# ssslidar_v1_0_blade_PWR_top.net
KiCad netlist of a schematic drawn in EAGLE
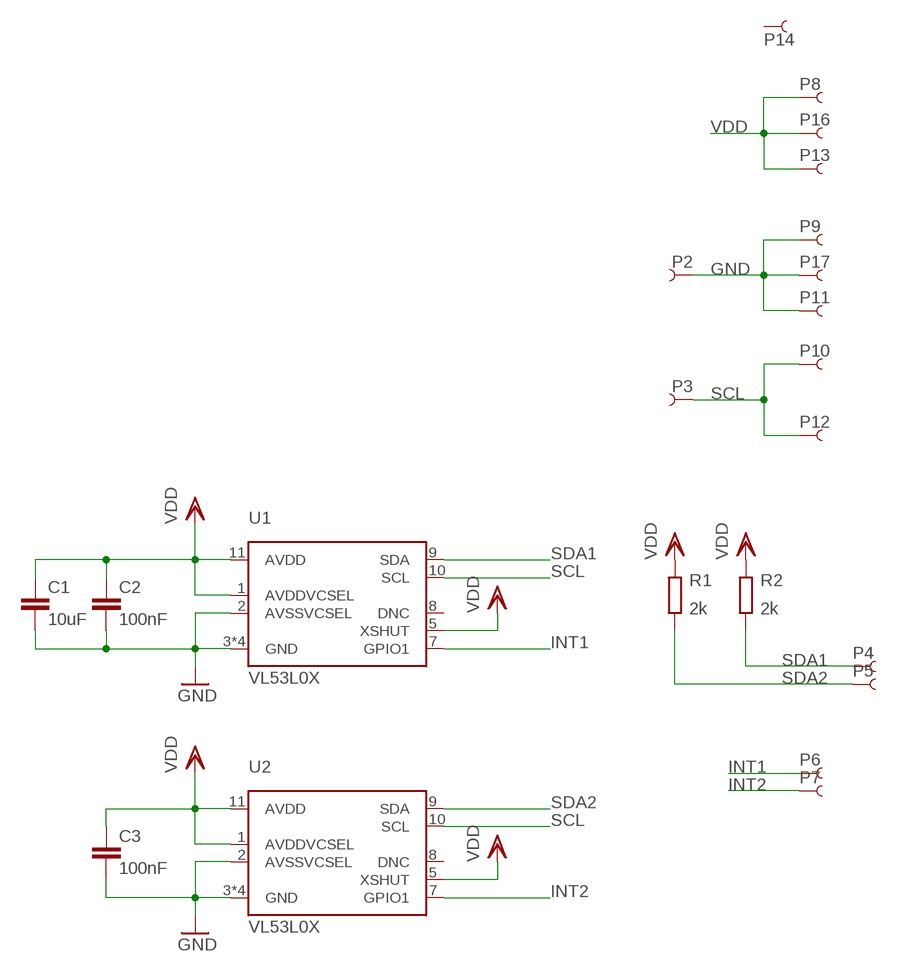
[diagram p0: schematic, sheet 1]

(export (version "E")
  (design (tool "Eeschema 10.0.6"))
  (components
    (comp (ref "C1")
      (value "10uF")
      (footprint "eagle-import:0805_N")
      (libsource (lib "eagle-import") (part "C0805"))
    )
    (comp (ref "C2")
      (value "100nF")
      (footprint "eagle-import:0402_N")
      (libsource (lib "eagle-import") (part "C0402"))
    )
    (comp (ref "C3")
      (value "100nF")
      (footprint "eagle-import:0402_N")
      (libsource (lib "eagle-import") (part "C0402"))
    )
    (comp (ref "P2")
      (value "PIN_SMD_1X1_RECT")
      (footprint "eagle-import:PIN_SMD_1X1_RECT")
      (libsource (lib "eagle-import") (part "PIN_SMD_1X1_RECT"))
    )
    (comp (ref "P3")
      (value "PIN_SMD_0.8X1_RECT")
      (footprint "eagle-import:PIN_SMD_0.8X1_RECT")
      (libsource (lib "eagle-import") (part "PIN_SMD_0.8X1_RECT"))
    )
    (comp (ref "P4")
      (value "PIN_SMD_0.8X1_RECT")
      (footprint "eagle-import:PIN_SMD_0.8X1_RECT")
      (libsource (lib "eagle-import") (part "PIN_SMD_0.8X1_RECT"))
    )
    (comp (ref "P5")
      (value "PIN_SMD_0.8X1_RECT")
      (footprint "eagle-import:PIN_SMD_0.8X1_RECT")
      (libsource (lib "eagle-import") (part "PIN_SMD_0.8X1_RECT"))
    )
    (comp (ref "P6")
      (value "PIN_SMD_0.8X1_RECT")
      (footprint "eagle-import:PIN_SMD_0.8X1_RECT")
      (libsource (lib "eagle-import") (part "PIN_SMD_0.8X1_RECT"))
    )
    (comp (ref "P7")
      (value "PIN_SMD_0.8X1_RECT")
      (footprint "eagle-import:PIN_SMD_0.8X1_RECT")
      (libsource (lib "eagle-import") (part "PIN_SMD_0.8X1_RECT"))
    )
    (comp (ref "P8")
      (value "PIN_SMD_0.8X1_RECT")
      (footprint "eagle-import:PIN_SMD_0.8X1_RECT")
      (libsource (lib "eagle-import") (part "PIN_SMD_0.8X1_RECT"))
    )
    (comp (ref "P9")
      (value "PIN_SMD_1X1_RECT")
      (footprint "eagle-import:PIN_SMD_1X1_RECT")
      (libsource (lib "eagle-import") (part "PIN_SMD_1X1_RECT"))
    )
    (comp (ref "P10")
      (value "PIN_SMD_1X1_RECT")
      (footprint "eagle-import:PIN_SMD_1X1_RECT")
      (libsource (lib "eagle-import") (part "PIN_SMD_1X1_RECT"))
    )
    (comp (ref "P11")
      (value "PIN_SMD_1X2")
      (footprint "eagle-import:PIN_SMD_1X2")
      (libsource (lib "eagle-import") (part "PIN_SMD_1X2"))
    )
    (comp (ref "P12")
      (value "PIN_SMD_1X1_RECT")
      (footprint "eagle-import:PIN_SMD_1X1_RECT")
      (libsource (lib "eagle-import") (part "PIN_SMD_1X1_RECT"))
    )
    (comp (ref "P13")
      (value "PIN_SMD_1X1_RECT")
      (footprint "eagle-import:PIN_SMD_1X1_RECT")
      (libsource (lib "eagle-import") (part "PIN_SMD_1X1_RECT"))
    )
    (comp (ref "P14")
      (value "PIN_SMD_0.8X1_RECT")
      (footprint "eagle-import:PIN_SMD_0.8X1_RECT")
      (libsource (lib "eagle-import") (part "PIN_SMD_0.8X1_RECT"))
    )
    (comp (ref "P16")
      (value "PIN_SMD_1X1_RECT")
      (footprint "eagle-import:PIN_SMD_1X1_RECT")
      (libsource (lib "eagle-import") (part "PIN_SMD_1X1_RECT"))
    )
    (comp (ref "P17")
      (value "PIN_SMD_1X2")
      (footprint "eagle-import:PIN_SMD_1X2")
      (libsource (lib "eagle-import") (part "PIN_SMD_1X2"))
    )
    (comp (ref "R1")
      (value "2k")
      (footprint "eagle-import:0402_N")
      (libsource (lib "eagle-import") (part "R0402"))
    )
    (comp (ref "R2")
      (value "2k")
      (footprint "eagle-import:0402_N")
      (libsource (lib "eagle-import") (part "R0402"))
    )
    (comp (ref "U1")
      (value "VL53L0X")
      (footprint "eagle-import:VL53L0X")
      (libsource (lib "eagle-import") (part "VL53L0X"))
    )
    (comp (ref "U2")
      (value "VL53L0X")
      (footprint "eagle-import:VL53L0X")
      (libsource (lib "eagle-import") (part "VL53L0X"))
    )
  )
  (nets
    (net (code "1") (name "/INT1") (class "Default")
      (node (ref "P6") (pin "PIN") (pinfunction "1_PIN") (pintype "bidirectional"))
      (node (ref "U1") (pin "7") (pinfunction "GPIO1_7") (pintype "bidirectional"))
    )
    (net (code "2") (name "/INT2") (class "Default")
      (node (ref "P7") (pin "PIN") (pinfunction "1_PIN") (pintype "bidirectional"))
      (node (ref "U2") (pin "7") (pinfunction "GPIO1_7") (pintype "bidirectional"))
    )
    (net (code "3") (name "/SCL") (class "Default")
      (node (ref "P10") (pin "PIN") (pinfunction "1_PIN") (pintype "bidirectional"))
      (node (ref "P12") (pin "PIN") (pinfunction "1_PIN") (pintype "bidirectional"))
      (node (ref "P3") (pin "PIN") (pinfunction "1_PIN") (pintype "bidirectional"))
      (node (ref "U1") (pin "10") (pinfunction "SCL_10") (pintype "bidirectional"))
      (node (ref "U2") (pin "10") (pinfunction "SCL_10") (pintype "bidirectional"))
    )
    (net (code "4") (name "/SDA1") (class "Default")
      (node (ref "P4") (pin "PIN") (pinfunction "1_PIN") (pintype "bidirectional"))
      (node (ref "R2") (pin "1") (pinfunction "1_1") (pintype "passive"))
      (node (ref "U1") (pin "9") (pinfunction "SDA_9") (pintype "bidirectional"))
    )
    (net (code "5") (name "/SDA2") (class "Default")
      (node (ref "P5") (pin "PIN") (pinfunction "1_PIN") (pintype "bidirectional"))
      (node (ref "R1") (pin "1") (pinfunction "1_1") (pintype "passive"))
      (node (ref "U2") (pin "9") (pinfunction "SDA_9") (pintype "bidirectional"))
    )
    (net (code "6") (name "GND") (class "Default")
      (node (ref "C1") (pin "2") (pinfunction "2_2") (pintype "passive"))
      (node (ref "C2") (pin "2") (pinfunction "2_2") (pintype "passive"))
      (node (ref "C3") (pin "2") (pinfunction "2_2") (pintype "passive"))
      (node (ref "P11") (pin "P$1") (pinfunction "1_P$1") (pintype "bidirectional"))
      (node (ref "P17") (pin "P$1") (pinfunction "1_P$1") (pintype "bidirectional"))
      (node (ref "P2") (pin "PIN") (pinfunction "1_PIN") (pintype "bidirectional"))
      (node (ref "P9") (pin "PIN") (pinfunction "1_PIN") (pintype "bidirectional"))
      (node (ref "U1") (pin "12") (pinfunction "GND_12") (pintype "bidirectional"))
      (node (ref "U1") (pin "2") (pinfunction "AVSSVCSEL_2") (pintype "bidirectional"))
      (node (ref "U1") (pin "3") (pinfunction "GND_3") (pintype "bidirectional"))
      (node (ref "U1") (pin "4") (pinfunction "GND_4") (pintype "bidirectional"))
      (node (ref "U1") (pin "6") (pinfunction "GND_6") (pintype "bidirectional"))
      (node (ref "U2") (pin "12") (pinfunction "GND_12") (pintype "bidirectional"))
      (node (ref "U2") (pin "2") (pinfunction "AVSSVCSEL_2") (pintype "bidirectional"))
      (node (ref "U2") (pin "3") (pinfunction "GND_3") (pintype "bidirectional"))
      (node (ref "U2") (pin "4") (pinfunction "GND_4") (pintype "bidirectional"))
      (node (ref "U2") (pin "6") (pinfunction "GND_6") (pintype "bidirectional"))
    )
    (net (code "7") (name "VDD") (class "Default")
      (node (ref "C1") (pin "1") (pinfunction "1_1") (pintype "passive"))
      (node (ref "C2") (pin "1") (pinfunction "1_1") (pintype "passive"))
      (node (ref "C3") (pin "1") (pinfunction "1_1") (pintype "passive"))
      (node (ref "P13") (pin "PIN") (pinfunction "1_PIN") (pintype "bidirectional"))
      (node (ref "P16") (pin "PIN") (pinfunction "1_PIN") (pintype "bidirectional"))
      (node (ref "P8") (pin "PIN") (pinfunction "1_PIN") (pintype "bidirectional"))
      (node (ref "R1") (pin "2") (pinfunction "2_2") (pintype "passive"))
      (node (ref "R2") (pin "2") (pinfunction "2_2") (pintype "passive"))
      (node (ref "U1") (pin "1") (pinfunction "AVDDVCSEL_1") (pintype "bidirectional"))
      (node (ref "U1") (pin "11") (pinfunction "AVDD_11") (pintype "bidirectional"))
      (node (ref "U1") (pin "5") (pinfunction "XSHUT_5") (pintype "bidirectional"))
      (node (ref "U2") (pin "1") (pinfunction "AVDDVCSEL_1") (pintype "bidirectional"))
      (node (ref "U2") (pin "11") (pinfunction "AVDD_11") (pintype "bidirectional"))
      (node (ref "U2") (pin "5") (pinfunction "XSHUT_5") (pintype "bidirectional"))
    )
    (net (code "8") (name "unconnected-(P14-1-PadPIN)") (class "Default")
      (node (ref "P14") (pin "PIN") (pinfunction "1_PIN") (pintype "bidirectional"))
    )
    (net (code "9") (name "unconnected-(U1-DNC-Pad8)") (class "Default")
      (node (ref "U1") (pin "8") (pinfunction "DNC_8") (pintype "bidirectional"))
    )
    (net (code "10") (name "unconnected-(U2-DNC-Pad8)") (class "Default")
      (node (ref "U2") (pin "8") (pinfunction "DNC_8") (pintype "bidirectional"))
    )
  )
)
